# esp32-ind-controller-r1.net
KiCad netlist of a schematic drawn in EAGLE
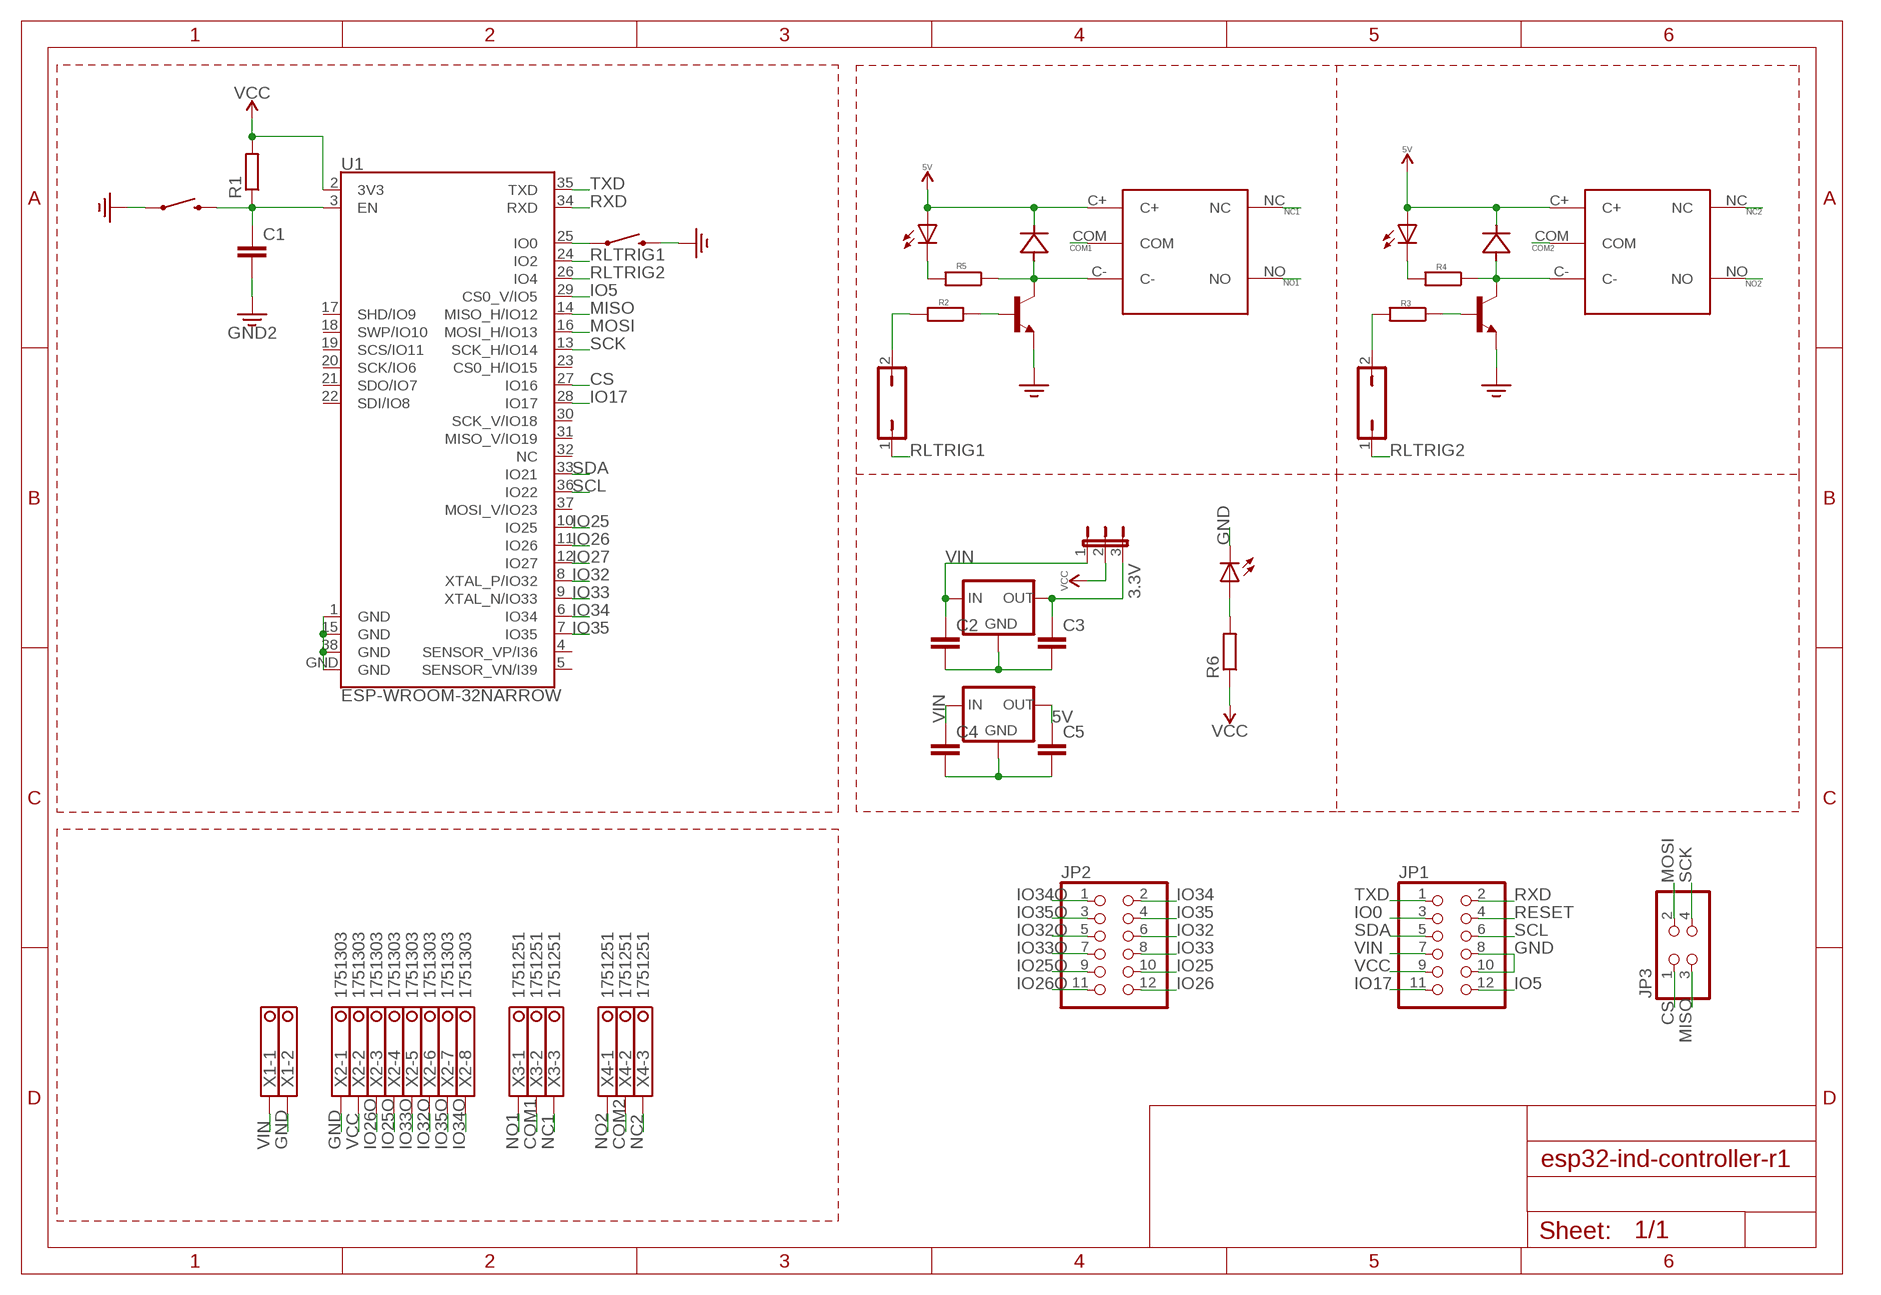
[diagram p0: schematic, sheet 1]

(export (version "E")
  (design (tool "Eeschema 10.0.6"))
  (components
    (comp (ref "C1")
      (value "C1206")
      (footprint "eagle-import:C1206")
      (libsource (lib "eagle-import") (part "C1206"))
    )
    (comp (ref "C2")
      (value "C1206")
      (footprint "eagle-import:C1206")
      (libsource (lib "eagle-import") (part "C1206"))
    )
    (comp (ref "C3")
      (value "C1206")
      (footprint "eagle-import:C1206")
      (libsource (lib "eagle-import") (part "C1206"))
    )
    (comp (ref "C4")
      (value "C1206")
      (footprint "eagle-import:C1206")
      (libsource (lib "eagle-import") (part "C1206"))
    )
    (comp (ref "C5")
      (value "C1206")
      (footprint "eagle-import:C1206")
      (libsource (lib "eagle-import") (part "C1206"))
    )
    (comp (ref "JP1")
      (value "PINHD-2X6")
      (footprint "eagle-import:2X06")
      (libsource (lib "eagle-import") (part "PINHD-2X6"))
    )
    (comp (ref "JP2")
      (value "PINHD-2X6")
      (footprint "eagle-import:2X06")
      (libsource (lib "eagle-import") (part "PINHD-2X6"))
    )
    (comp (ref "JP3")
      (value "PINHD-2X2")
      (footprint "eagle-import:2X02")
      (libsource (lib "eagle-import") (part "PINHD-2X2"))
    )
    (comp (ref "R1")
      (value "R1206")
      (footprint "eagle-import:R1206")
      (libsource (lib "eagle-import") (part "R1206"))
    )
    (comp (ref "R2")
      (value "R1206")
      (footprint "eagle-import:R1206")
      (libsource (lib "eagle-import") (part "R1206"))
    )
    (comp (ref "R3")
      (value "R1206")
      (footprint "eagle-import:R1206")
      (libsource (lib "eagle-import") (part "R1206"))
    )
    (comp (ref "R4")
      (value "R1206")
      (footprint "eagle-import:R1206")
      (libsource (lib "eagle-import") (part "R1206"))
    )
    (comp (ref "R5")
      (value "R1206")
      (footprint "eagle-import:R1206")
      (libsource (lib "eagle-import") (part "R1206"))
    )
    (comp (ref "R6")
      (value "R1206")
      (footprint "eagle-import:R1206")
      (libsource (lib "eagle-import") (part "R1206"))
    )
    (comp (ref "U$1")
      (value "RELAY-SONGLE-05V")
      (footprint "eagle-import:RELAY-SONGLE-05V")
      (libsource (lib "eagle-import") (part "RELAY-SONGLE-05V"))
    )
    (comp (ref "U$2")
      (value "RELAY-SONGLE-05V")
      (footprint "eagle-import:RELAY-SONGLE-05V")
      (libsource (lib "eagle-import") (part "RELAY-SONGLE-05V"))
    )
    (comp (ref "U$3")
      (value "TACT-SW-SMD")
      (footprint "eagle-import:TACTILE_SWITCH_SMD_6.0X3.5MM")
      (libsource (lib "eagle-import") (part "TACT-SW-SMD"))
    )
    (comp (ref "U$4")
      (value "TACT-SW-SMD")
      (footprint "eagle-import:TACTILE_SWITCH_SMD_6.0X3.5MM")
      (libsource (lib "eagle-import") (part "TACT-SW-SMD"))
    )
    (comp (ref "U$5")
      (value "MBR0520_DIODE")
      (footprint "eagle-import:SOD123")
      (libsource (lib "eagle-import") (part "MBR0520_DIODE"))
    )
    (comp (ref "U$6")
      (value "MMBT3904_NPN_TRAN")
      (footprint "eagle-import:SOT23")
      (libsource (lib "eagle-import") (part "MMBT3904_NPN_TRAN"))
    )
    (comp (ref "U$7")
      (value "MMBT3904_NPN_TRAN")
      (footprint "eagle-import:SOT23")
      (libsource (lib "eagle-import") (part "MMBT3904_NPN_TRAN"))
    )
    (comp (ref "U$8")
      (value "MBR0520_DIODE")
      (footprint "eagle-import:SOD123")
      (libsource (lib "eagle-import") (part "MBR0520_DIODE"))
    )
    (comp (ref "U$9")
      (value "CHIPLED_1206GREEN")
      (footprint "eagle-import:CHIPLED_1206_GRN")
      (libsource (lib "eagle-import") (part "CHIPLED_1206GREEN"))
    )
    (comp (ref "U$10")
      (value "CHIPLED_1206GREEN")
      (footprint "eagle-import:CHIPLED_1206_GRN")
      (libsource (lib "eagle-import") (part "CHIPLED_1206GREEN"))
    )
    (comp (ref "U$11")
      (value "JP-2")
      (footprint "eagle-import:JP2")
      (libsource (lib "eagle-import") (part "JP-2"))
    )
    (comp (ref "U$12")
      (value "LD1117-SOT223")
      (footprint "eagle-import:SOT223")
      (libsource (lib "eagle-import") (part "LD1117-SOT223"))
    )
    (comp (ref "U$13")
      (value "CHIPLED_1206GREEN")
      (footprint "eagle-import:CHIPLED_1206_GRN")
      (libsource (lib "eagle-import") (part "CHIPLED_1206GREEN"))
    )
    (comp (ref "U$14")
      (value "LD1117-SOT223")
      (footprint "eagle-import:SOT223")
      (libsource (lib "eagle-import") (part "LD1117-SOT223"))
    )
    (comp (ref "U$15")
      (value "JP-1")
      (footprint "eagle-import:JP1")
      (libsource (lib "eagle-import") (part "JP-1"))
    )
    (comp (ref "U$16")
      (value "JP-1")
      (footprint "eagle-import:JP1")
      (libsource (lib "eagle-import") (part "JP-1"))
    )
    (comp (ref "U1")
      (value "ESP-WROOM-32NARROW")
      (footprint "eagle-import:ESP-WROOM-32-NARROW")
      (libsource (lib "eagle-import") (part "ESP-WROOM-32NARROW"))
    )
    (comp (ref "X1")
      (value "1751248")
      (footprint "eagle-import:1751248")
      (libsource (lib "eagle-import") (part "1751248"))
    )
    (comp (ref "X2")
      (value "1751303")
      (footprint "eagle-import:1751303")
      (libsource (lib "eagle-import") (part "1751303"))
    )
    (comp (ref "X3")
      (value "1751251")
      (footprint "eagle-import:1751251")
      (libsource (lib "eagle-import") (part "1751251"))
    )
    (comp (ref "X4")
      (value "1751251")
      (footprint "eagle-import:1751251")
      (libsource (lib "eagle-import") (part "1751251"))
    )
  )
  (nets
    (net (code "1") (name "/3.3V") (class "Default")
      (node (ref "C3") (pin "1") (pinfunction "1_1") (pintype "passive"))
      (node (ref "U$11") (pin "3") (pinfunction "3_3") (pintype "passive"))
      (node (ref "U$12") (pin "2") (pinfunction "OUT_2") (pintype "passive"))
      (node (ref "U$12") (pin "4") (pinfunction "OUT_4") (pintype "passive"))
    )
    (net (code "2") (name "/COM1") (class "Default")
      (node (ref "U$1") (pin "COM") (pinfunction "COM_COM") (pintype "bidirectional"))
      (node (ref "X3") (pin "2") (pinfunction "K_2") (pintype "passive"))
    )
    (net (code "3") (name "/COM2") (class "Default")
      (node (ref "U$2") (pin "COM") (pinfunction "COM_COM") (pintype "bidirectional"))
      (node (ref "X4") (pin "2") (pinfunction "K_2") (pintype "passive"))
    )
    (net (code "4") (name "/CS") (class "Default")
      (node (ref "JP3") (pin "1") (pinfunction "1_1") (pintype "passive"))
      (node (ref "U1") (pin "27") (pinfunction "IO16_27") (pintype "bidirectional"))
    )
    (net (code "5") (name "/IO0") (class "Default")
      (node (ref "JP1") (pin "3") (pinfunction "3_3") (pintype "passive"))
      (node (ref "U$4") (pin "1") (pinfunction "1_1") (pintype "passive"))
      (node (ref "U1") (pin "25") (pinfunction "IO0_25") (pintype "bidirectional"))
    )
    (net (code "6") (name "/IO5") (class "Default")
      (node (ref "JP1") (pin "12") (pinfunction "12_12") (pintype "passive"))
      (node (ref "U1") (pin "29") (pinfunction "CS0_V/IO5_29") (pintype "bidirectional"))
    )
    (net (code "7") (name "/IO17") (class "Default")
      (node (ref "JP1") (pin "11") (pinfunction "11_11") (pintype "passive"))
      (node (ref "U1") (pin "28") (pinfunction "IO17_28") (pintype "bidirectional"))
    )
    (net (code "8") (name "/IO25") (class "Default")
      (node (ref "JP2") (pin "10") (pinfunction "10_10") (pintype "passive"))
      (node (ref "U1") (pin "10") (pinfunction "IO25_10") (pintype "bidirectional"))
    )
    (net (code "9") (name "/IO25O") (class "Default")
      (node (ref "JP2") (pin "9") (pinfunction "9_9") (pintype "passive"))
      (node (ref "X2") (pin "4") (pinfunction "K_4") (pintype "passive"))
    )
    (net (code "10") (name "/IO26") (class "Default")
      (node (ref "JP2") (pin "12") (pinfunction "12_12") (pintype "passive"))
      (node (ref "U1") (pin "11") (pinfunction "IO26_11") (pintype "bidirectional"))
    )
    (net (code "11") (name "/IO26O") (class "Default")
      (node (ref "JP2") (pin "11") (pinfunction "11_11") (pintype "passive"))
      (node (ref "X2") (pin "3") (pinfunction "K_3") (pintype "passive"))
    )
    (net (code "12") (name "/IO27") (class "Default")
      (node (ref "U1") (pin "12") (pinfunction "IO27_12") (pintype "bidirectional"))
    )
    (net (code "13") (name "/IO32") (class "Default")
      (node (ref "JP2") (pin "6") (pinfunction "6_6") (pintype "passive"))
      (node (ref "U1") (pin "8") (pinfunction "XTAL_P/IO32_8") (pintype "bidirectional"))
    )
    (net (code "14") (name "/IO32O") (class "Default")
      (node (ref "JP2") (pin "5") (pinfunction "5_5") (pintype "passive"))
      (node (ref "X2") (pin "6") (pinfunction "K_6") (pintype "passive"))
    )
    (net (code "15") (name "/IO33") (class "Default")
      (node (ref "JP2") (pin "8") (pinfunction "8_8") (pintype "passive"))
      (node (ref "U1") (pin "9") (pinfunction "XTAL_N/IO33_9") (pintype "bidirectional"))
    )
    (net (code "16") (name "/IO33O") (class "Default")
      (node (ref "JP2") (pin "7") (pinfunction "7_7") (pintype "passive"))
      (node (ref "X2") (pin "5") (pinfunction "K_5") (pintype "passive"))
    )
    (net (code "17") (name "/IO34") (class "Default")
      (node (ref "JP2") (pin "2") (pinfunction "2_2") (pintype "passive"))
      (node (ref "U1") (pin "6") (pinfunction "IO34_6") (pintype "bidirectional"))
    )
    (net (code "18") (name "/IO34O") (class "Default")
      (node (ref "JP2") (pin "1") (pinfunction "1_1") (pintype "passive"))
      (node (ref "X2") (pin "8") (pinfunction "K_8") (pintype "passive"))
    )
    (net (code "19") (name "/IO35") (class "Default")
      (node (ref "JP2") (pin "4") (pinfunction "4_4") (pintype "passive"))
      (node (ref "U1") (pin "7") (pinfunction "IO35_7") (pintype "bidirectional"))
    )
    (net (code "20") (name "/IO35O") (class "Default")
      (node (ref "JP2") (pin "3") (pinfunction "3_3") (pintype "passive"))
      (node (ref "X2") (pin "7") (pinfunction "K_7") (pintype "passive"))
    )
    (net (code "21") (name "/MISO") (class "Default")
      (node (ref "JP3") (pin "3") (pinfunction "3_3") (pintype "passive"))
      (node (ref "U1") (pin "14") (pinfunction "MISO_H/IO12_14") (pintype "bidirectional"))
    )
    (net (code "22") (name "/MOSI") (class "Default")
      (node (ref "JP3") (pin "2") (pinfunction "2_2") (pintype "passive"))
      (node (ref "U1") (pin "16") (pinfunction "MOSI_H/IO13_16") (pintype "bidirectional"))
    )
    (net (code "23") (name "/NC1") (class "Default")
      (node (ref "U$1") (pin "NC") (pinfunction "NC_NC") (pintype "bidirectional"))
      (node (ref "X3") (pin "3") (pinfunction "K_3") (pintype "passive"))
    )
    (net (code "24") (name "/NC2") (class "Default")
      (node (ref "U$2") (pin "NC") (pinfunction "NC_NC") (pintype "bidirectional"))
      (node (ref "X4") (pin "3") (pinfunction "K_3") (pintype "passive"))
    )
    (net (code "25") (name "/NO1") (class "Default")
      (node (ref "U$1") (pin "NO") (pinfunction "NO_NO") (pintype "bidirectional"))
      (node (ref "X3") (pin "1") (pinfunction "K_1") (pintype "passive"))
    )
    (net (code "26") (name "/NO2") (class "Default")
      (node (ref "U$2") (pin "NO") (pinfunction "NO_NO") (pintype "bidirectional"))
      (node (ref "X4") (pin "1") (pinfunction "K_1") (pintype "passive"))
    )
    (net (code "27") (name "/RESET") (class "Default")
      (node (ref "C1") (pin "1") (pinfunction "1_1") (pintype "passive"))
      (node (ref "JP1") (pin "4") (pinfunction "4_4") (pintype "passive"))
      (node (ref "R1") (pin "1") (pinfunction "1_1") (pintype "passive"))
      (node (ref "U$3") (pin "2") (pinfunction "2_2") (pintype "passive"))
      (node (ref "U1") (pin "3") (pinfunction "EN_3") (pintype "bidirectional"))
    )
    (net (code "28") (name "/RLTRIG1") (class "Default")
      (node (ref "U$16") (pin "1") (pinfunction "1_1") (pintype "passive"))
      (node (ref "U1") (pin "24") (pinfunction "IO2_24") (pintype "bidirectional"))
    )
    (net (code "29") (name "/RLTRIG2") (class "Default")
      (node (ref "U$15") (pin "1") (pinfunction "1_1") (pintype "passive"))
      (node (ref "U1") (pin "26") (pinfunction "IO4_26") (pintype "bidirectional"))
    )
    (net (code "30") (name "/RXD") (class "Default")
      (node (ref "JP1") (pin "2") (pinfunction "2_2") (pintype "passive"))
      (node (ref "U1") (pin "34") (pinfunction "RXD_34") (pintype "bidirectional"))
    )
    (net (code "31") (name "/SCK") (class "Default")
      (node (ref "JP3") (pin "4") (pinfunction "4_4") (pintype "passive"))
      (node (ref "U1") (pin "13") (pinfunction "SCK_H/IO14_13") (pintype "bidirectional"))
    )
    (net (code "32") (name "/SCL") (class "Default")
      (node (ref "JP1") (pin "6") (pinfunction "6_6") (pintype "passive"))
      (node (ref "U1") (pin "36") (pinfunction "IO22_36") (pintype "bidirectional"))
    )
    (net (code "33") (name "/SDA") (class "Default")
      (node (ref "JP1") (pin "5") (pinfunction "5_5") (pintype "passive"))
      (node (ref "U1") (pin "33") (pinfunction "IO21_33") (pintype "bidirectional"))
    )
    (net (code "34") (name "/TXD") (class "Default")
      (node (ref "JP1") (pin "1") (pinfunction "1_1") (pintype "passive"))
      (node (ref "U1") (pin "35") (pinfunction "TXD_35") (pintype "bidirectional"))
    )
    (net (code "35") (name "/VIN") (class "Default")
      (node (ref "C2") (pin "1") (pinfunction "1_1") (pintype "passive"))
      (node (ref "C4") (pin "1") (pinfunction "1_1") (pintype "passive"))
      (node (ref "JP1") (pin "7") (pinfunction "7_7") (pintype "passive"))
      (node (ref "U$11") (pin "1") (pinfunction "1_1") (pintype "passive"))
      (node (ref "U$12") (pin "3") (pinfunction "IN_3") (pintype "input"))
      (node (ref "U$14") (pin "3") (pinfunction "IN_3") (pintype "input"))
      (node (ref "X1") (pin "1") (pinfunction "K_1") (pintype "passive"))
    )
    (net (code "36") (name "5V") (class "Default")
      (node (ref "C5") (pin "1") (pinfunction "1_1") (pintype "passive"))
      (node (ref "U$1") (pin "C+") (pinfunction "C+_C+") (pintype "bidirectional"))
      (node (ref "U$10") (pin "A") (pinfunction "A_A") (pintype "passive"))
      (node (ref "U$14") (pin "2") (pinfunction "OUT_2") (pintype "passive"))
      (node (ref "U$14") (pin "4") (pinfunction "OUT_4") (pintype "passive"))
      (node (ref "U$2") (pin "C+") (pinfunction "C+_C+") (pintype "bidirectional"))
      (node (ref "U$5") (pin "C") (pinfunction "C_C") (pintype "passive"))
      (node (ref "U$8") (pin "C") (pinfunction "C_C") (pintype "passive"))
      (node (ref "U$9") (pin "A") (pinfunction "A_A") (pintype "passive"))
    )
    (net (code "37") (name "GND2") (class "Default")
      (node (ref "C1") (pin "2") (pinfunction "2_2") (pintype "passive"))
      (node (ref "C2") (pin "2") (pinfunction "2_2") (pintype "passive"))
      (node (ref "C3") (pin "2") (pinfunction "2_2") (pintype "passive"))
      (node (ref "C4") (pin "2") (pinfunction "2_2") (pintype "passive"))
      (node (ref "C5") (pin "2") (pinfunction "2_2") (pintype "passive"))
      (node (ref "JP1") (pin "10") (pinfunction "10_10") (pintype "passive"))
      (node (ref "JP1") (pin "8") (pinfunction "8_8") (pintype "passive"))
      (node (ref "U$12") (pin "1") (pinfunction "GND_1") (pintype "input"))
      (node (ref "U$13") (pin "C") (pinfunction "C_C") (pintype "passive"))
      (node (ref "U$14") (pin "1") (pinfunction "GND_1") (pintype "input"))
      (node (ref "U$3") (pin "1") (pinfunction "1_1") (pintype "passive"))
      (node (ref "U$4") (pin "2") (pinfunction "2_2") (pintype "passive"))
      (node (ref "U$6") (pin "2") (pinfunction "E_2") (pintype "passive"))
      (node (ref "U$7") (pin "2") (pinfunction "E_2") (pintype "passive"))
      (node (ref "U1") (pin "1") (pinfunction "GND_1") (pintype "bidirectional"))
      (node (ref "U1") (pin "15") (pinfunction "GND_15") (pintype "bidirectional"))
      (node (ref "U1") (pin "38") (pinfunction "GND_38") (pintype "bidirectional"))
      (node (ref "U1") (pin "GND") (pinfunction "GND_GND") (pintype "bidirectional"))
      (node (ref "X1") (pin "2") (pinfunction "K_2") (pintype "passive"))
      (node (ref "X2") (pin "1") (pinfunction "K_1") (pintype "passive"))
    )
    (net (code "38") (name "Net-(R2-Pad2)") (class "Default")
      (node (ref "R2") (pin "2") (pinfunction "2_2") (pintype "passive"))
      (node (ref "U$16") (pin "2") (pinfunction "2_2") (pintype "passive"))
    )
    (net (code "39") (name "Net-(R3-Pad2)") (class "Default")
      (node (ref "R3") (pin "2") (pinfunction "2_2") (pintype "passive"))
      (node (ref "U$15") (pin "2") (pinfunction "2_2") (pintype "passive"))
    )
    (net (code "40") (name "Net-(R4-Pad2)") (class "Default")
      (node (ref "R4") (pin "2") (pinfunction "2_2") (pintype "passive"))
      (node (ref "U$9") (pin "C") (pinfunction "C_C") (pintype "passive"))
    )
    (net (code "41") (name "Net-(R5-Pad2)") (class "Default")
      (node (ref "R5") (pin "2") (pinfunction "2_2") (pintype "passive"))
      (node (ref "U$10") (pin "C") (pinfunction "C_C") (pintype "passive"))
    )
    (net (code "42") (name "Net-(R6-Pad2)") (class "Default")
      (node (ref "R6") (pin "2") (pinfunction "2_2") (pintype "passive"))
      (node (ref "U$13") (pin "A") (pinfunction "A_A") (pintype "passive"))
    )
    (net (code "43") (name "Net-(U$6-B)") (class "Default")
      (node (ref "R2") (pin "1") (pinfunction "1_1") (pintype "passive"))
      (node (ref "U$6") (pin "1") (pinfunction "B_1") (pintype "passive"))
    )
    (net (code "44") (name "Net-(U$6-C)") (class "Default")
      (node (ref "R5") (pin "1") (pinfunction "1_1") (pintype "passive"))
      (node (ref "U$1") (pin "C-") (pinfunction "C-_C-") (pintype "bidirectional"))
      (node (ref "U$5") (pin "A") (pinfunction "A_A") (pintype "passive"))
      (node (ref "U$6") (pin "3") (pinfunction "C_3") (pintype "passive"))
    )
    (net (code "45") (name "Net-(U$7-B)") (class "Default")
      (node (ref "R3") (pin "1") (pinfunction "1_1") (pintype "passive"))
      (node (ref "U$7") (pin "1") (pinfunction "B_1") (pintype "passive"))
    )
    (net (code "46") (name "Net-(U$7-C)") (class "Default")
      (node (ref "R4") (pin "1") (pinfunction "1_1") (pintype "passive"))
      (node (ref "U$2") (pin "C-") (pinfunction "C-_C-") (pintype "bidirectional"))
      (node (ref "U$7") (pin "3") (pinfunction "C_3") (pintype "passive"))
      (node (ref "U$8") (pin "A") (pinfunction "A_A") (pintype "passive"))
    )
    (net (code "47") (name "VCC") (class "Default")
      (node (ref "JP1") (pin "9") (pinfunction "9_9") (pintype "passive"))
      (node (ref "R1") (pin "2") (pinfunction "2_2") (pintype "passive"))
      (node (ref "R6") (pin "1") (pinfunction "1_1") (pintype "passive"))
      (node (ref "U$11") (pin "2") (pinfunction "2_2") (pintype "passive"))
      (node (ref "U1") (pin "2") (pinfunction "3V3_2") (pintype "bidirectional"))
      (node (ref "X2") (pin "2") (pinfunction "K_2") (pintype "passive"))
    )
    (net (code "48") (name "unconnected-(U1-CS0_H{slash}IO15-Pad23)") (class "Default")
      (node (ref "U1") (pin "23") (pinfunction "CS0_H/IO15_23") (pintype "bidirectional"))
    )
    (net (code "49") (name "unconnected-(U1-MISO_V{slash}IO19-Pad31)") (class "Default")
      (node (ref "U1") (pin "31") (pinfunction "MISO_V/IO19_31") (pintype "bidirectional"))
    )
    (net (code "50") (name "unconnected-(U1-MOSI_V{slash}IO23-Pad37)") (class "Default")
      (node (ref "U1") (pin "37") (pinfunction "MOSI_V/IO23_37") (pintype "bidirectional"))
    )
    (net (code "51") (name "unconnected-(U1-NC-Pad32)") (class "Default")
      (node (ref "U1") (pin "32") (pinfunction "NC_32") (pintype "bidirectional"))
    )
    (net (code "52") (name "unconnected-(U1-SCK_V{slash}IO18-Pad30)") (class "Default")
      (node (ref "U1") (pin "30") (pinfunction "SCK_V/IO18_30") (pintype "bidirectional"))
    )
    (net (code "53") (name "unconnected-(U1-SCK{slash}IO6-Pad20)") (class "Default")
      (node (ref "U1") (pin "20") (pinfunction "SCK/IO6_20") (pintype "bidirectional"))
    )
    (net (code "54") (name "unconnected-(U1-SCS{slash}IO11-Pad19)") (class "Default")
      (node (ref "U1") (pin "19") (pinfunction "SCS/IO11_19") (pintype "bidirectional"))
    )
    (net (code "55") (name "unconnected-(U1-SDI{slash}IO8-Pad22)") (class "Default")
      (node (ref "U1") (pin "22") (pinfunction "SDI/IO8_22") (pintype "bidirectional"))
    )
    (net (code "56") (name "unconnected-(U1-SDO{slash}IO7-Pad21)") (class "Default")
      (node (ref "U1") (pin "21") (pinfunction "SDO/IO7_21") (pintype "bidirectional"))
    )
    (net (code "57") (name "unconnected-(U1-SENSOR_VN{slash}I39-Pad5)") (class "Default")
      (node (ref "U1") (pin "5") (pinfunction "SENSOR_VN/I39_5") (pintype "bidirectional"))
    )
    (net (code "58") (name "unconnected-(U1-SENSOR_VP{slash}I36-Pad4)") (class "Default")
      (node (ref "U1") (pin "4") (pinfunction "SENSOR_VP/I36_4") (pintype "bidirectional"))
    )
    (net (code "59") (name "unconnected-(U1-SHD{slash}IO9-Pad17)") (class "Default")
      (node (ref "U1") (pin "17") (pinfunction "SHD/IO9_17") (pintype "bidirectional"))
    )
    (net (code "60") (name "unconnected-(U1-SWP{slash}IO10-Pad18)") (class "Default")
      (node (ref "U1") (pin "18") (pinfunction "SWP/IO10_18") (pintype "bidirectional"))
    )
  )
)
